# DummyLoad_SCH.net
KiCad netlist of a schematic drawn in Altium Designer
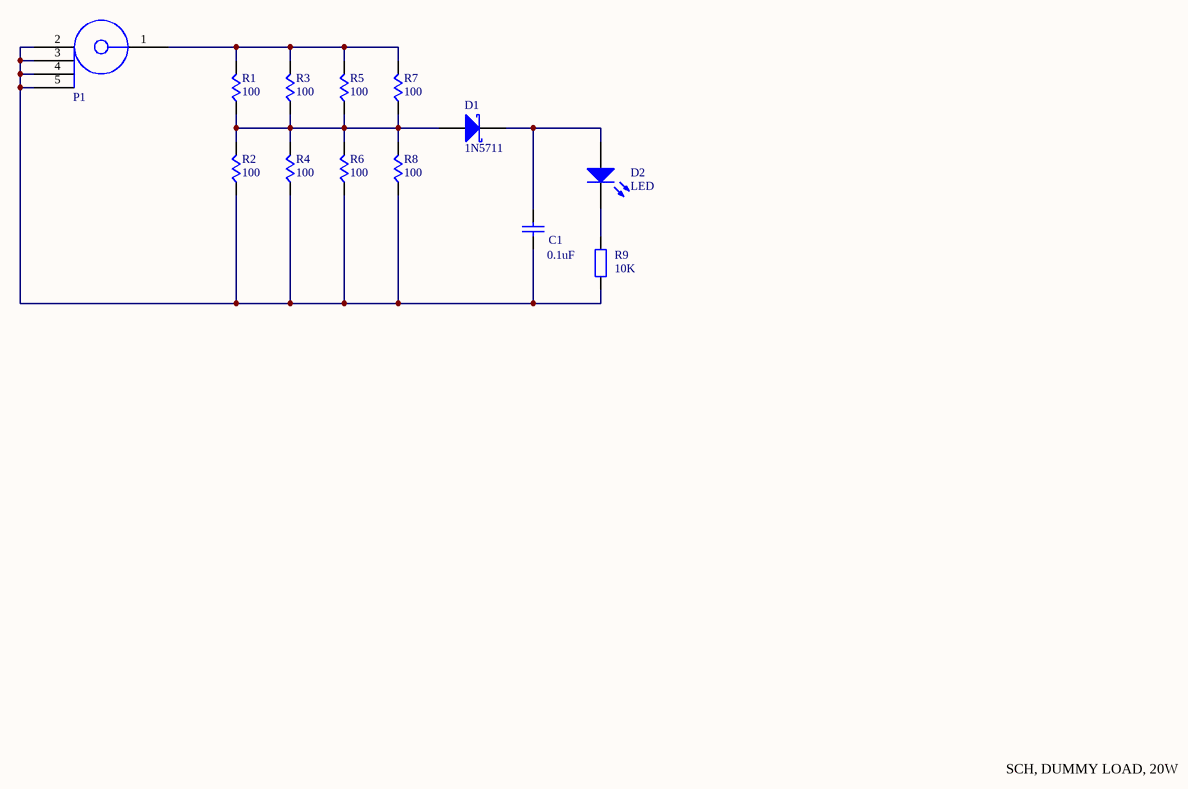
[diagram p0: DummyLoad_SCH.SchDoc]

(export (version "E")
  (design (tool "Eeschema 10.0.6"))
  (components
    (comp (ref "C1")
      (value "0.1uF")
      (footprint "CAP_AR20")
      (fields (field (name "TOLERANCE") "20%") (field (name "VOLTAGE") "50V") (field (name "Comment") "CAP"))
      (libsource (lib "ATHELA_Library") (part "CAP"))
    )
    (comp (ref "D1")
      (value "1N5711")
      (footprint "STM-DO-35-2")
      (description "Small Signal Schottky Diode, 70 V, -65 to 200 degC, 2-Pin THD (DO-35), RoHs, Tape and Reel")
      (fields (field (name "MANUFACTURER") "STMicroelectronics") (field (name "Comment") "Diode"))
      (libsource (lib "ATHELA_Library") (part "Diode"))
    )
    (comp (ref "D2")
      (value "LED")
      (footprint "Type 5mm")
      (description "THT LED round mono-color color lens, WL-TMRW, Red")
      (fields (field (name "PARTNUMBER") "151051RS11000") (field (name "MANUFACTURER") "Wuerth Elektronik"))
      (libsource (lib "ATHELA_Library") (part "LED"))
    )
    (comp (ref "P1")
      (value "CONN_BNC")
      (footprint "CONN_5-1634513-1")
      (libsource (lib "ATHELA_Library") (part "CONN_BNC"))
    )
    (comp (ref "R1")
      (value "100")
      (footprint "Axial 0.8")
      (description "Resistor")
      (fields (field (name "TOLERANCE") "5%") (field (name "Comment") "R"))
      (libsource (lib "MAST_Library") (part "R"))
    )
    (comp (ref "R2")
      (value "100")
      (footprint "Axial 0.8")
      (description "Resistor")
      (fields (field (name "TOLERANCE") "5%") (field (name "Comment") "R"))
      (libsource (lib "MAST_Library") (part "R"))
    )
    (comp (ref "R3")
      (value "100")
      (footprint "Axial 0.8")
      (description "Resistor")
      (fields (field (name "TOLERANCE") "5%") (field (name "Comment") "R"))
      (libsource (lib "MAST_Library") (part "R"))
    )
    (comp (ref "R4")
      (value "100")
      (footprint "Axial 0.8")
      (description "Resistor")
      (fields (field (name "TOLERANCE") "5%") (field (name "Comment") "R"))
      (libsource (lib "MAST_Library") (part "R"))
    )
    (comp (ref "R5")
      (value "100")
      (footprint "Axial 0.8")
      (description "Resistor")
      (fields (field (name "TOLERANCE") "5%") (field (name "Comment") "R"))
      (libsource (lib "MAST_Library") (part "R"))
    )
    (comp (ref "R6")
      (value "100")
      (footprint "Axial 0.8")
      (description "Resistor")
      (fields (field (name "TOLERANCE") "5%") (field (name "Comment") "R"))
      (libsource (lib "MAST_Library") (part "R"))
    )
    (comp (ref "R7")
      (value "100")
      (footprint "Axial 0.8")
      (description "Resistor")
      (fields (field (name "TOLERANCE") "5%") (field (name "Comment") "R"))
      (libsource (lib "MAST_Library") (part "R"))
    )
    (comp (ref "R8")
      (value "100")
      (footprint "Axial 0.8")
      (description "Resistor")
      (fields (field (name "TOLERANCE") "5%") (field (name "Comment") "R"))
      (libsource (lib "MAST_Library") (part "R"))
    )
    (comp (ref "R9")
      (value "10K")
      (footprint "AXIAL-0.4")
      (description "Resistor")
      (fields (field (name "TOLERANCE") "5%") (field (name "PUBLISHER") "Altium Limited"))
      (libsource (lib "Miscellaneous Devices") (part "Res2"))
    )
  )
  (nets
    (net (code "1") (name "Net-(C1-Pad1)") (class "Default")
      (node (ref "C1") (pin "1") (pinfunction "1_1") (pintype "passive"))
      (node (ref "P1") (pin "2") (pinfunction "2_2") (pintype "passive"))
      (node (ref "P1") (pin "3") (pinfunction "3_3") (pintype "passive"))
      (node (ref "P1") (pin "4") (pinfunction "4_4") (pintype "passive"))
      (node (ref "P1") (pin "5") (pinfunction "5_5") (pintype "passive"))
      (node (ref "R2") (pin "1") (pinfunction "1_1") (pintype "passive"))
      (node (ref "R4") (pin "1") (pinfunction "1_1") (pintype "passive"))
      (node (ref "R6") (pin "1") (pinfunction "1_1") (pintype "passive"))
      (node (ref "R8") (pin "1") (pinfunction "1_1") (pintype "passive"))
      (node (ref "R9") (pin "1") (pinfunction "1_1") (pintype "passive"))
    )
    (net (code "2") (name "Net-(D1-A)") (class "Default")
      (node (ref "D1") (pin "1") (pinfunction "A_1") (pintype "passive"))
      (node (ref "R1") (pin "1") (pinfunction "1_1") (pintype "passive"))
      (node (ref "R2") (pin "2") (pinfunction "2_2") (pintype "passive"))
      (node (ref "R3") (pin "1") (pinfunction "1_1") (pintype "passive"))
      (node (ref "R4") (pin "2") (pinfunction "2_2") (pintype "passive"))
      (node (ref "R5") (pin "1") (pinfunction "1_1") (pintype "passive"))
      (node (ref "R6") (pin "2") (pinfunction "2_2") (pintype "passive"))
      (node (ref "R7") (pin "1") (pinfunction "1_1") (pintype "passive"))
      (node (ref "R8") (pin "2") (pinfunction "2_2") (pintype "passive"))
    )
    (net (code "3") (name "Net-(D1-K)") (class "Default")
      (node (ref "C1") (pin "2") (pinfunction "2_2") (pintype "passive"))
      (node (ref "D1") (pin "2") (pinfunction "K_2") (pintype "passive"))
      (node (ref "D2") (pin "2") (pinfunction "A_2") (pintype "passive"))
    )
    (net (code "4") (name "Net-(D2-K)") (class "Default")
      (node (ref "D2") (pin "1") (pinfunction "K_1") (pintype "passive"))
      (node (ref "R9") (pin "2") (pinfunction "2_2") (pintype "passive"))
    )
    (net (code "5") (name "Net-(P1-Pad1)") (class "Default")
      (node (ref "P1") (pin "1") (pinfunction "1_1") (pintype "passive"))
      (node (ref "R1") (pin "2") (pinfunction "2_2") (pintype "passive"))
      (node (ref "R3") (pin "2") (pinfunction "2_2") (pintype "passive"))
      (node (ref "R5") (pin "2") (pinfunction "2_2") (pintype "passive"))
      (node (ref "R7") (pin "2") (pinfunction "2_2") (pintype "passive"))
    )
  )
)
